# SRAMShield_sch.net
KiCad netlist of a schematic drawn in EAGLE
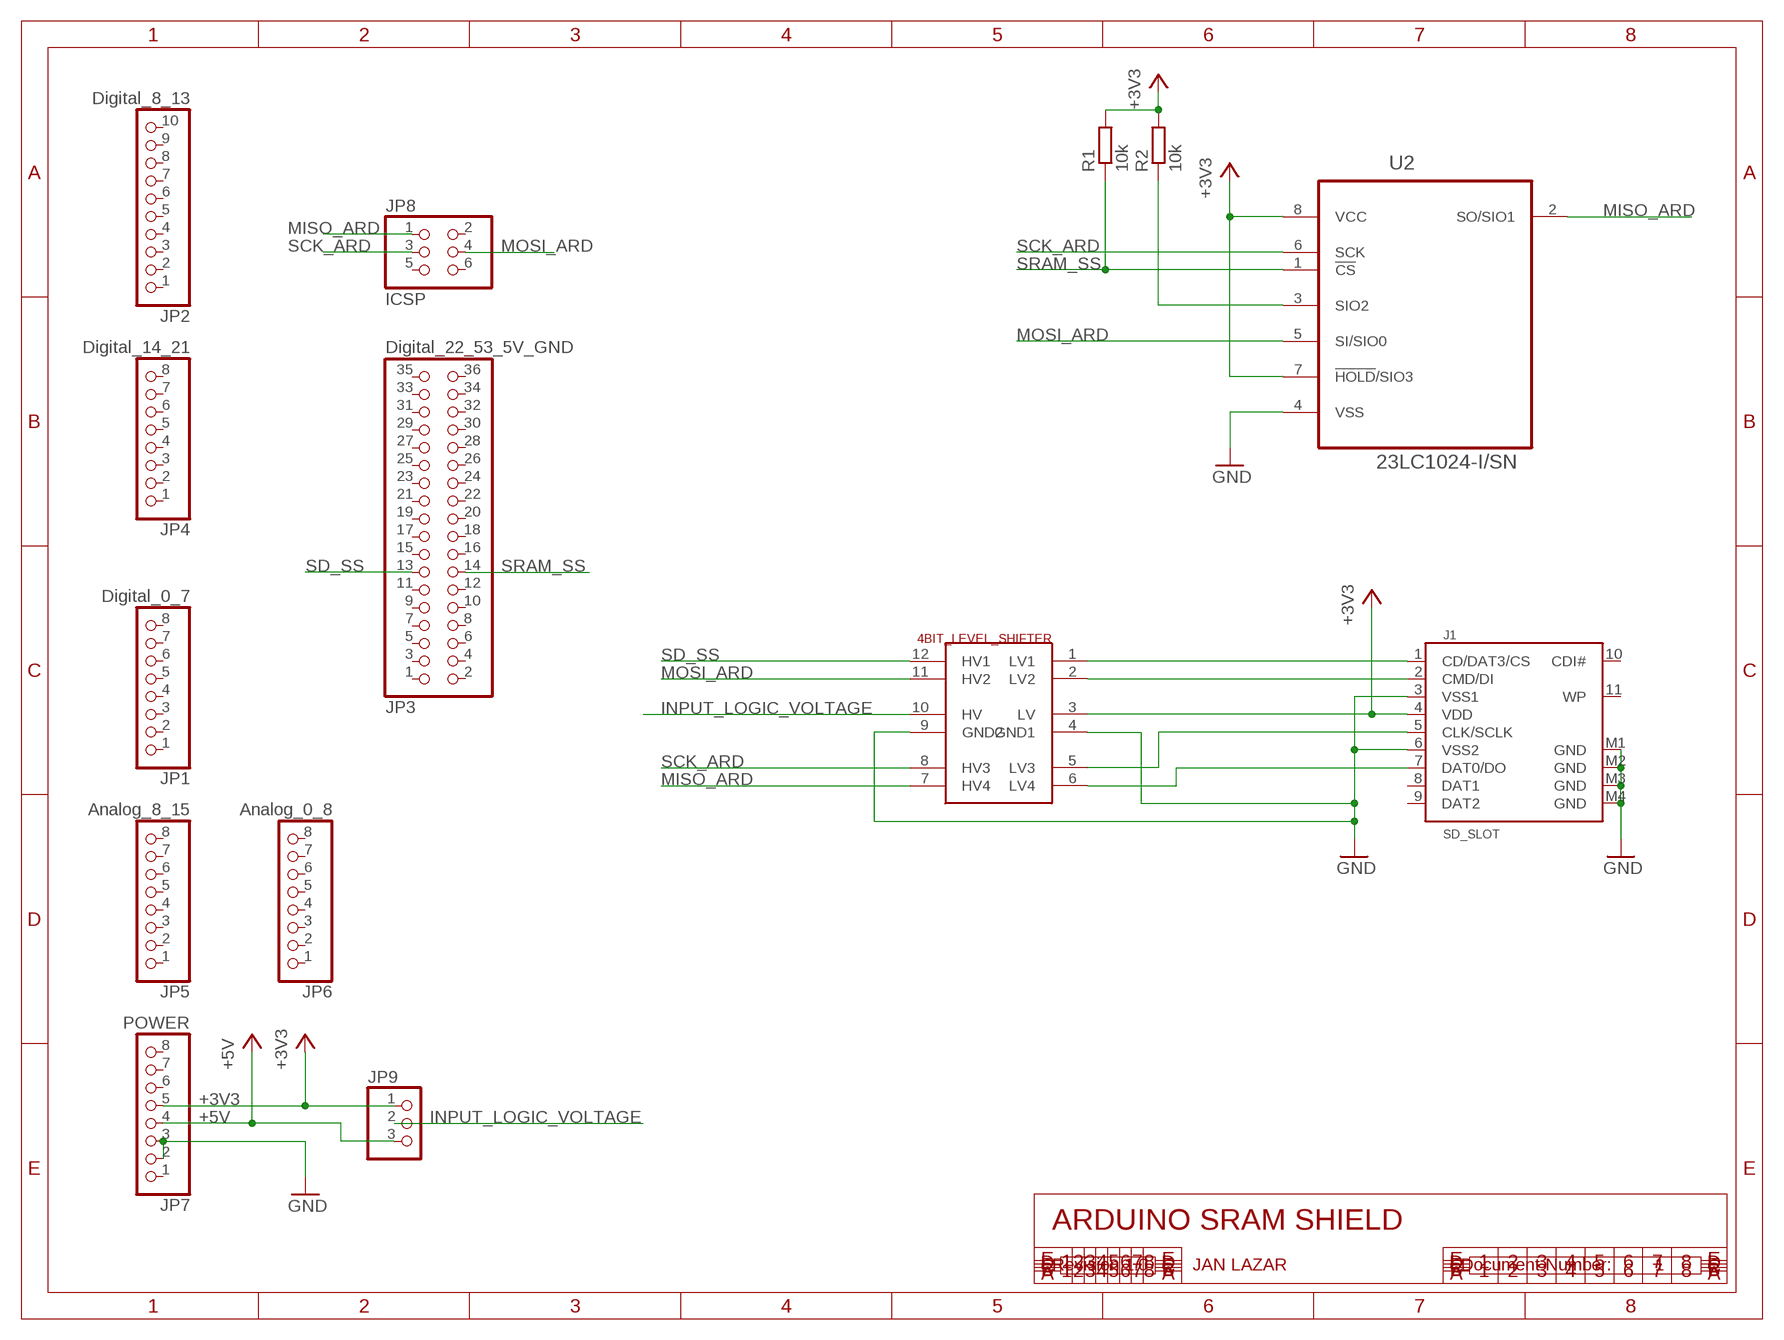
[diagram p0: schematic, sheet 1]

(export (version "E")
  (design (tool "Eeschema 10.0.6"))
  (components
    (comp (ref "4BIT_LEVEL_SHIFTER")
      (value "4BIT_LEVEL_SHIFTER")
      (footprint "eagle-import:THT12")
      (libsource (lib "eagle-import") (part "4BIT_LEVEL_SHIFTER"))
    )
    (comp (ref "J1")
      (value "SD_SLOT")
      (footprint "eagle-import:SDCMF-10915W010")
      (libsource (lib "eagle-import") (part "SDCARD"))
    )
    (comp (ref "JP1")
      (value "Digital_0_7")
      (footprint "eagle-import:1X08")
      (libsource (lib "eagle-import") (part "PINHD-1X8"))
    )
    (comp (ref "JP2")
      (value "Digital_8_13")
      (footprint "eagle-import:1X10")
      (libsource (lib "eagle-import") (part "PINHD-1X10"))
    )
    (comp (ref "JP3")
      (value "Digital_22_53_5V_GND")
      (footprint "eagle-import:2X18")
      (libsource (lib "eagle-import") (part "PINHD-2X18"))
    )
    (comp (ref "JP4")
      (value "Digital_14_21")
      (footprint "eagle-import:1X08")
      (libsource (lib "eagle-import") (part "PINHD-1X8"))
    )
    (comp (ref "JP5")
      (value "Analog_8_15")
      (footprint "eagle-import:1X08")
      (libsource (lib "eagle-import") (part "PINHD-1X8"))
    )
    (comp (ref "JP6")
      (value "Analog_0_8")
      (footprint "eagle-import:1X08")
      (libsource (lib "eagle-import") (part "PINHD-1X8"))
    )
    (comp (ref "JP7")
      (value "POWER")
      (footprint "eagle-import:1X08")
      (libsource (lib "eagle-import") (part "PINHD-1X8"))
    )
    (comp (ref "JP8")
      (value "ICSP")
      (footprint "eagle-import:2X03")
      (libsource (lib "eagle-import") (part "PINHD-2X3"))
    )
    (comp (ref "JP9")
      (value "PINHD-1X3")
      (footprint "eagle-import:1X03")
      (libsource (lib "eagle-import") (part "PINHD-1X3"))
    )
    (comp (ref "R1")
      (value "10k")
      (footprint "eagle-import:0204_7")
      (libsource (lib "eagle-import") (part "R-EU_0204/7"))
    )
    (comp (ref "R2")
      (value "10k")
      (footprint "eagle-import:0204_7")
      (libsource (lib "eagle-import") (part "R-EU_0204/7"))
    )
    (comp (ref "U2")
      (value "23LC1024-I/SN")
      (footprint "eagle-import:SOIC127P600X175-8N")
      (libsource (lib "eagle-import") (part "23LC1024-I/SN"))
    )
  )
  (nets
    (net (code "1") (name "+3V3") (class "Default")
      (node (ref "4BIT_LEVEL_SHIFTER") (pin "3") (pinfunction "LV_3") (pintype "bidirectional"))
      (node (ref "J1") (pin "4") (pinfunction "VDD_4") (pintype "power_in"))
      (node (ref "JP7") (pin "5") (pinfunction "5_5") (pintype "passive"))
      (node (ref "JP9") (pin "1") (pinfunction "1_1") (pintype "passive"))
      (node (ref "R1") (pin "2") (pinfunction "2_2") (pintype "passive"))
      (node (ref "R2") (pin "2") (pinfunction "2_2") (pintype "passive"))
      (node (ref "U2") (pin "7") (pinfunction "~{HOLD}/SIO3_7") (pintype "passive"))
      (node (ref "U2") (pin "8") (pinfunction "VCC_8") (pintype "power_in"))
    )
    (net (code "2") (name "+5V") (class "Default")
      (node (ref "JP7") (pin "4") (pinfunction "4_4") (pintype "passive"))
      (node (ref "JP9") (pin "3") (pinfunction "3_3") (pintype "passive"))
    )
    (net (code "3") (name "/INPUT_LOGIC_VOLTAGE") (class "Default")
      (node (ref "4BIT_LEVEL_SHIFTER") (pin "10") (pinfunction "HV_10") (pintype "bidirectional"))
      (node (ref "JP9") (pin "2") (pinfunction "2_2") (pintype "passive"))
    )
    (net (code "4") (name "/MISO_ARD") (class "Default")
      (node (ref "4BIT_LEVEL_SHIFTER") (pin "7") (pinfunction "HV4_7") (pintype "bidirectional"))
      (node (ref "JP8") (pin "1") (pinfunction "1_1") (pintype "passive"))
      (node (ref "U2") (pin "2") (pinfunction "SO/SIO1_2") (pintype "output"))
    )
    (net (code "5") (name "/MOSI_ARD") (class "Default")
      (node (ref "4BIT_LEVEL_SHIFTER") (pin "11") (pinfunction "HV2_11") (pintype "bidirectional"))
      (node (ref "JP8") (pin "4") (pinfunction "4_4") (pintype "passive"))
      (node (ref "U2") (pin "5") (pinfunction "SI/SIO0_5") (pintype "input"))
    )
    (net (code "6") (name "/SCK_ARD") (class "Default")
      (node (ref "4BIT_LEVEL_SHIFTER") (pin "8") (pinfunction "HV3_8") (pintype "bidirectional"))
      (node (ref "JP8") (pin "3") (pinfunction "3_3") (pintype "passive"))
      (node (ref "U2") (pin "6") (pinfunction "SCK_6") (pintype "input"))
    )
    (net (code "7") (name "/SD_SS") (class "Default")
      (node (ref "4BIT_LEVEL_SHIFTER") (pin "12") (pinfunction "HV1_12") (pintype "bidirectional"))
      (node (ref "JP3") (pin "13") (pinfunction "13_13") (pintype "passive"))
    )
    (net (code "8") (name "/SRAM_SS") (class "Default")
      (node (ref "JP3") (pin "14") (pinfunction "14_14") (pintype "passive"))
      (node (ref "R1") (pin "1") (pinfunction "1_1") (pintype "passive"))
      (node (ref "U2") (pin "1") (pinfunction "~{CS}_1") (pintype "input"))
    )
    (net (code "9") (name "GND") (class "Default")
      (node (ref "4BIT_LEVEL_SHIFTER") (pin "4") (pinfunction "GND1_4") (pintype "bidirectional"))
      (node (ref "4BIT_LEVEL_SHIFTER") (pin "9") (pinfunction "GND2_9") (pintype "bidirectional"))
      (node (ref "J1") (pin "3") (pinfunction "VSS1_3") (pintype "power_in"))
      (node (ref "J1") (pin "6") (pinfunction "VSS2_6") (pintype "power_in"))
      (node (ref "J1") (pin "M1") (pinfunction "GND_M1") (pintype "power_in"))
      (node (ref "J1") (pin "M2") (pinfunction "GND_M2") (pintype "power_in"))
      (node (ref "J1") (pin "M3") (pinfunction "GND_M3") (pintype "power_in"))
      (node (ref "J1") (pin "M4") (pinfunction "GND_M4") (pintype "power_in"))
      (node (ref "JP7") (pin "2") (pinfunction "2_2") (pintype "passive"))
      (node (ref "JP7") (pin "3") (pinfunction "3_3") (pintype "passive"))
      (node (ref "U2") (pin "4") (pinfunction "VSS_4") (pintype "passive"))
    )
    (net (code "10") (name "Net-(4BIT_LEVEL_SHIFTER-LV1)") (class "Default")
      (node (ref "4BIT_LEVEL_SHIFTER") (pin "1") (pinfunction "LV1_1") (pintype "bidirectional"))
      (node (ref "J1") (pin "1") (pinfunction "CD/DAT3/CS_1") (pintype "bidirectional"))
    )
    (net (code "11") (name "Net-(4BIT_LEVEL_SHIFTER-LV2)") (class "Default")
      (node (ref "4BIT_LEVEL_SHIFTER") (pin "2") (pinfunction "LV2_2") (pintype "bidirectional"))
      (node (ref "J1") (pin "2") (pinfunction "CMD/DI_2") (pintype "bidirectional"))
    )
    (net (code "12") (name "Net-(4BIT_LEVEL_SHIFTER-LV3)") (class "Default")
      (node (ref "4BIT_LEVEL_SHIFTER") (pin "5") (pinfunction "LV3_5") (pintype "bidirectional"))
      (node (ref "J1") (pin "5") (pinfunction "CLK/SCLK_5") (pintype "bidirectional"))
    )
    (net (code "13") (name "Net-(4BIT_LEVEL_SHIFTER-LV4)") (class "Default")
      (node (ref "4BIT_LEVEL_SHIFTER") (pin "6") (pinfunction "LV4_6") (pintype "bidirectional"))
      (node (ref "J1") (pin "7") (pinfunction "DAT0/DO_7") (pintype "bidirectional"))
    )
    (net (code "14") (name "Net-(U2-SIO2)") (class "Default")
      (node (ref "R2") (pin "1") (pinfunction "1_1") (pintype "passive"))
      (node (ref "U2") (pin "3") (pinfunction "SIO2_3") (pintype "passive"))
    )
    (net (code "15") (name "unconnected-(J1-CDI#-Pad10)") (class "Default")
      (node (ref "J1") (pin "10") (pinfunction "CDI#_10") (pintype "output"))
    )
    (net (code "16") (name "unconnected-(J1-DAT1-Pad8)") (class "Default")
      (node (ref "J1") (pin "8") (pinfunction "DAT1_8") (pintype "bidirectional"))
    )
    (net (code "17") (name "unconnected-(J1-DAT2-Pad9)") (class "Default")
      (node (ref "J1") (pin "9") (pinfunction "DAT2_9") (pintype "bidirectional"))
    )
    (net (code "18") (name "unconnected-(J1-WP-Pad11)") (class "Default")
      (node (ref "J1") (pin "11") (pinfunction "WP_11") (pintype "output"))
    )
    (net (code "19") (name "unconnected-(JP1-Pad1)") (class "Default")
      (node (ref "JP1") (pin "1") (pinfunction "1_1") (pintype "passive"))
    )
    (net (code "20") (name "unconnected-(JP1-Pad2)") (class "Default")
      (node (ref "JP1") (pin "2") (pinfunction "2_2") (pintype "passive"))
    )
    (net (code "21") (name "unconnected-(JP1-Pad3)") (class "Default")
      (node (ref "JP1") (pin "3") (pinfunction "3_3") (pintype "passive"))
    )
    (net (code "22") (name "unconnected-(JP1-Pad4)") (class "Default")
      (node (ref "JP1") (pin "4") (pinfunction "4_4") (pintype "passive"))
    )
    (net (code "23") (name "unconnected-(JP1-Pad5)") (class "Default")
      (node (ref "JP1") (pin "5") (pinfunction "5_5") (pintype "passive"))
    )
    (net (code "24") (name "unconnected-(JP1-Pad6)") (class "Default")
      (node (ref "JP1") (pin "6") (pinfunction "6_6") (pintype "passive"))
    )
    (net (code "25") (name "unconnected-(JP1-Pad7)") (class "Default")
      (node (ref "JP1") (pin "7") (pinfunction "7_7") (pintype "passive"))
    )
    (net (code "26") (name "unconnected-(JP1-Pad8)") (class "Default")
      (node (ref "JP1") (pin "8") (pinfunction "8_8") (pintype "passive"))
    )
    (net (code "27") (name "unconnected-(JP2-Pad1)") (class "Default")
      (node (ref "JP2") (pin "1") (pinfunction "1_1") (pintype "passive"))
    )
    (net (code "28") (name "unconnected-(JP2-Pad2)") (class "Default")
      (node (ref "JP2") (pin "2") (pinfunction "2_2") (pintype "passive"))
    )
    (net (code "29") (name "unconnected-(JP2-Pad3)") (class "Default")
      (node (ref "JP2") (pin "3") (pinfunction "3_3") (pintype "passive"))
    )
    (net (code "30") (name "unconnected-(JP2-Pad4)") (class "Default")
      (node (ref "JP2") (pin "4") (pinfunction "4_4") (pintype "passive"))
    )
    (net (code "31") (name "unconnected-(JP2-Pad5)") (class "Default")
      (node (ref "JP2") (pin "5") (pinfunction "5_5") (pintype "passive"))
    )
    (net (code "32") (name "unconnected-(JP2-Pad6)") (class "Default")
      (node (ref "JP2") (pin "6") (pinfunction "6_6") (pintype "passive"))
    )
    (net (code "33") (name "unconnected-(JP2-Pad7)") (class "Default")
      (node (ref "JP2") (pin "7") (pinfunction "7_7") (pintype "passive"))
    )
    (net (code "34") (name "unconnected-(JP2-Pad8)") (class "Default")
      (node (ref "JP2") (pin "8") (pinfunction "8_8") (pintype "passive"))
    )
    (net (code "35") (name "unconnected-(JP2-Pad9)") (class "Default")
      (node (ref "JP2") (pin "9") (pinfunction "9_9") (pintype "passive"))
    )
    (net (code "36") (name "unconnected-(JP2-Pad10)") (class "Default")
      (node (ref "JP2") (pin "10") (pinfunction "10_10") (pintype "passive"))
    )
    (net (code "37") (name "unconnected-(JP3-Pad1)") (class "Default")
      (node (ref "JP3") (pin "1") (pinfunction "1_1") (pintype "passive"))
    )
    (net (code "38") (name "unconnected-(JP3-Pad2)") (class "Default")
      (node (ref "JP3") (pin "2") (pinfunction "2_2") (pintype "passive"))
    )
    (net (code "39") (name "unconnected-(JP3-Pad3)") (class "Default")
      (node (ref "JP3") (pin "3") (pinfunction "3_3") (pintype "passive"))
    )
    (net (code "40") (name "unconnected-(JP3-Pad4)") (class "Default")
      (node (ref "JP3") (pin "4") (pinfunction "4_4") (pintype "passive"))
    )
    (net (code "41") (name "unconnected-(JP3-Pad5)") (class "Default")
      (node (ref "JP3") (pin "5") (pinfunction "5_5") (pintype "passive"))
    )
    (net (code "42") (name "unconnected-(JP3-Pad6)") (class "Default")
      (node (ref "JP3") (pin "6") (pinfunction "6_6") (pintype "passive"))
    )
    (net (code "43") (name "unconnected-(JP3-Pad7)") (class "Default")
      (node (ref "JP3") (pin "7") (pinfunction "7_7") (pintype "passive"))
    )
    (net (code "44") (name "unconnected-(JP3-Pad8)") (class "Default")
      (node (ref "JP3") (pin "8") (pinfunction "8_8") (pintype "passive"))
    )
    (net (code "45") (name "unconnected-(JP3-Pad9)") (class "Default")
      (node (ref "JP3") (pin "9") (pinfunction "9_9") (pintype "passive"))
    )
    (net (code "46") (name "unconnected-(JP3-Pad10)") (class "Default")
      (node (ref "JP3") (pin "10") (pinfunction "10_10") (pintype "passive"))
    )
    (net (code "47") (name "unconnected-(JP3-Pad11)") (class "Default")
      (node (ref "JP3") (pin "11") (pinfunction "11_11") (pintype "passive"))
    )
    (net (code "48") (name "unconnected-(JP3-Pad12)") (class "Default")
      (node (ref "JP3") (pin "12") (pinfunction "12_12") (pintype "passive"))
    )
    (net (code "49") (name "unconnected-(JP3-Pad15)") (class "Default")
      (node (ref "JP3") (pin "15") (pinfunction "15_15") (pintype "passive"))
    )
    (net (code "50") (name "unconnected-(JP3-Pad16)") (class "Default")
      (node (ref "JP3") (pin "16") (pinfunction "16_16") (pintype "passive"))
    )
    (net (code "51") (name "unconnected-(JP3-Pad17)") (class "Default")
      (node (ref "JP3") (pin "17") (pinfunction "17_17") (pintype "passive"))
    )
    (net (code "52") (name "unconnected-(JP3-Pad18)") (class "Default")
      (node (ref "JP3") (pin "18") (pinfunction "18_18") (pintype "passive"))
    )
    (net (code "53") (name "unconnected-(JP3-Pad19)") (class "Default")
      (node (ref "JP3") (pin "19") (pinfunction "19_19") (pintype "passive"))
    )
    (net (code "54") (name "unconnected-(JP3-Pad20)") (class "Default")
      (node (ref "JP3") (pin "20") (pinfunction "20_20") (pintype "passive"))
    )
    (net (code "55") (name "unconnected-(JP3-Pad21)") (class "Default")
      (node (ref "JP3") (pin "21") (pinfunction "21_21") (pintype "passive"))
    )
    (net (code "56") (name "unconnected-(JP3-Pad22)") (class "Default")
      (node (ref "JP3") (pin "22") (pinfunction "22_22") (pintype "passive"))
    )
    (net (code "57") (name "unconnected-(JP3-Pad23)") (class "Default")
      (node (ref "JP3") (pin "23") (pinfunction "23_23") (pintype "passive"))
    )
    (net (code "58") (name "unconnected-(JP3-Pad24)") (class "Default")
      (node (ref "JP3") (pin "24") (pinfunction "24_24") (pintype "passive"))
    )
    (net (code "59") (name "unconnected-(JP3-Pad25)") (class "Default")
      (node (ref "JP3") (pin "25") (pinfunction "25_25") (pintype "passive"))
    )
    (net (code "60") (name "unconnected-(JP3-Pad26)") (class "Default")
      (node (ref "JP3") (pin "26") (pinfunction "26_26") (pintype "passive"))
    )
    (net (code "61") (name "unconnected-(JP3-Pad27)") (class "Default")
      (node (ref "JP3") (pin "27") (pinfunction "27_27") (pintype "passive"))
    )
    (net (code "62") (name "unconnected-(JP3-Pad28)") (class "Default")
      (node (ref "JP3") (pin "28") (pinfunction "28_28") (pintype "passive"))
    )
    (net (code "63") (name "unconnected-(JP3-Pad29)") (class "Default")
      (node (ref "JP3") (pin "29") (pinfunction "29_29") (pintype "passive"))
    )
    (net (code "64") (name "unconnected-(JP3-Pad30)") (class "Default")
      (node (ref "JP3") (pin "30") (pinfunction "30_30") (pintype "passive"))
    )
    (net (code "65") (name "unconnected-(JP3-Pad31)") (class "Default")
      (node (ref "JP3") (pin "31") (pinfunction "31_31") (pintype "passive"))
    )
    (net (code "66") (name "unconnected-(JP3-Pad32)") (class "Default")
      (node (ref "JP3") (pin "32") (pinfunction "32_32") (pintype "passive"))
    )
    (net (code "67") (name "unconnected-(JP3-Pad33)") (class "Default")
      (node (ref "JP3") (pin "33") (pinfunction "33_33") (pintype "passive"))
    )
    (net (code "68") (name "unconnected-(JP3-Pad34)") (class "Default")
      (node (ref "JP3") (pin "34") (pinfunction "34_34") (pintype "passive"))
    )
    (net (code "69") (name "unconnected-(JP3-Pad35)") (class "Default")
      (node (ref "JP3") (pin "35") (pinfunction "35_35") (pintype "passive"))
    )
    (net (code "70") (name "unconnected-(JP3-Pad36)") (class "Default")
      (node (ref "JP3") (pin "36") (pinfunction "36_36") (pintype "passive"))
    )
    (net (code "71") (name "unconnected-(JP4-Pad1)") (class "Default")
      (node (ref "JP4") (pin "1") (pinfunction "1_1") (pintype "passive"))
    )
    (net (code "72") (name "unconnected-(JP4-Pad2)") (class "Default")
      (node (ref "JP4") (pin "2") (pinfunction "2_2") (pintype "passive"))
    )
    (net (code "73") (name "unconnected-(JP4-Pad3)") (class "Default")
      (node (ref "JP4") (pin "3") (pinfunction "3_3") (pintype "passive"))
    )
    (net (code "74") (name "unconnected-(JP4-Pad4)") (class "Default")
      (node (ref "JP4") (pin "4") (pinfunction "4_4") (pintype "passive"))
    )
    (net (code "75") (name "unconnected-(JP4-Pad5)") (class "Default")
      (node (ref "JP4") (pin "5") (pinfunction "5_5") (pintype "passive"))
    )
    (net (code "76") (name "unconnected-(JP4-Pad6)") (class "Default")
      (node (ref "JP4") (pin "6") (pinfunction "6_6") (pintype "passive"))
    )
    (net (code "77") (name "unconnected-(JP4-Pad7)") (class "Default")
      (node (ref "JP4") (pin "7") (pinfunction "7_7") (pintype "passive"))
    )
    (net (code "78") (name "unconnected-(JP4-Pad8)") (class "Default")
      (node (ref "JP4") (pin "8") (pinfunction "8_8") (pintype "passive"))
    )
    (net (code "79") (name "unconnected-(JP5-Pad1)") (class "Default")
      (node (ref "JP5") (pin "1") (pinfunction "1_1") (pintype "passive"))
    )
    (net (code "80") (name "unconnected-(JP5-Pad2)") (class "Default")
      (node (ref "JP5") (pin "2") (pinfunction "2_2") (pintype "passive"))
    )
    (net (code "81") (name "unconnected-(JP5-Pad3)") (class "Default")
      (node (ref "JP5") (pin "3") (pinfunction "3_3") (pintype "passive"))
    )
    (net (code "82") (name "unconnected-(JP5-Pad4)") (class "Default")
      (node (ref "JP5") (pin "4") (pinfunction "4_4") (pintype "passive"))
    )
    (net (code "83") (name "unconnected-(JP5-Pad5)") (class "Default")
      (node (ref "JP5") (pin "5") (pinfunction "5_5") (pintype "passive"))
    )
    (net (code "84") (name "unconnected-(JP5-Pad6)") (class "Default")
      (node (ref "JP5") (pin "6") (pinfunction "6_6") (pintype "passive"))
    )
    (net (code "85") (name "unconnected-(JP5-Pad7)") (class "Default")
      (node (ref "JP5") (pin "7") (pinfunction "7_7") (pintype "passive"))
    )
    (net (code "86") (name "unconnected-(JP5-Pad8)") (class "Default")
      (node (ref "JP5") (pin "8") (pinfunction "8_8") (pintype "passive"))
    )
    (net (code "87") (name "unconnected-(JP6-Pad1)") (class "Default")
      (node (ref "JP6") (pin "1") (pinfunction "1_1") (pintype "passive"))
    )
    (net (code "88") (name "unconnected-(JP6-Pad2)") (class "Default")
      (node (ref "JP6") (pin "2") (pinfunction "2_2") (pintype "passive"))
    )
    (net (code "89") (name "unconnected-(JP6-Pad3)") (class "Default")
      (node (ref "JP6") (pin "3") (pinfunction "3_3") (pintype "passive"))
    )
    (net (code "90") (name "unconnected-(JP6-Pad4)") (class "Default")
      (node (ref "JP6") (pin "4") (pinfunction "4_4") (pintype "passive"))
    )
    (net (code "91") (name "unconnected-(JP6-Pad5)") (class "Default")
      (node (ref "JP6") (pin "5") (pinfunction "5_5") (pintype "passive"))
    )
    (net (code "92") (name "unconnected-(JP6-Pad6)") (class "Default")
      (node (ref "JP6") (pin "6") (pinfunction "6_6") (pintype "passive"))
    )
    (net (code "93") (name "unconnected-(JP6-Pad7)") (class "Default")
      (node (ref "JP6") (pin "7") (pinfunction "7_7") (pintype "passive"))
    )
    (net (code "94") (name "unconnected-(JP6-Pad8)") (class "Default")
      (node (ref "JP6") (pin "8") (pinfunction "8_8") (pintype "passive"))
    )
    (net (code "95") (name "unconnected-(JP7-Pad1)") (class "Default")
      (node (ref "JP7") (pin "1") (pinfunction "1_1") (pintype "passive"))
    )
    (net (code "96") (name "unconnected-(JP7-Pad6)") (class "Default")
      (node (ref "JP7") (pin "6") (pinfunction "6_6") (pintype "passive"))
    )
    (net (code "97") (name "unconnected-(JP7-Pad7)") (class "Default")
      (node (ref "JP7") (pin "7") (pinfunction "7_7") (pintype "passive"))
    )
    (net (code "98") (name "unconnected-(JP7-Pad8)") (class "Default")
      (node (ref "JP7") (pin "8") (pinfunction "8_8") (pintype "passive"))
    )
    (net (code "99") (name "unconnected-(JP8-Pad2)") (class "Default")
      (node (ref "JP8") (pin "2") (pinfunction "2_2") (pintype "passive"))
    )
    (net (code "100") (name "unconnected-(JP8-Pad5)") (class "Default")
      (node (ref "JP8") (pin "5") (pinfunction "5_5") (pintype "passive"))
    )
    (net (code "101") (name "unconnected-(JP8-Pad6)") (class "Default")
      (node (ref "JP8") (pin "6") (pinfunction "6_6") (pintype "passive"))
    )
  )
)
